# NBP5_Actel_ProASIC_Plus_PQ208_Rev1_01.net
KiCad netlist of a schematic drawn in Altium Designer
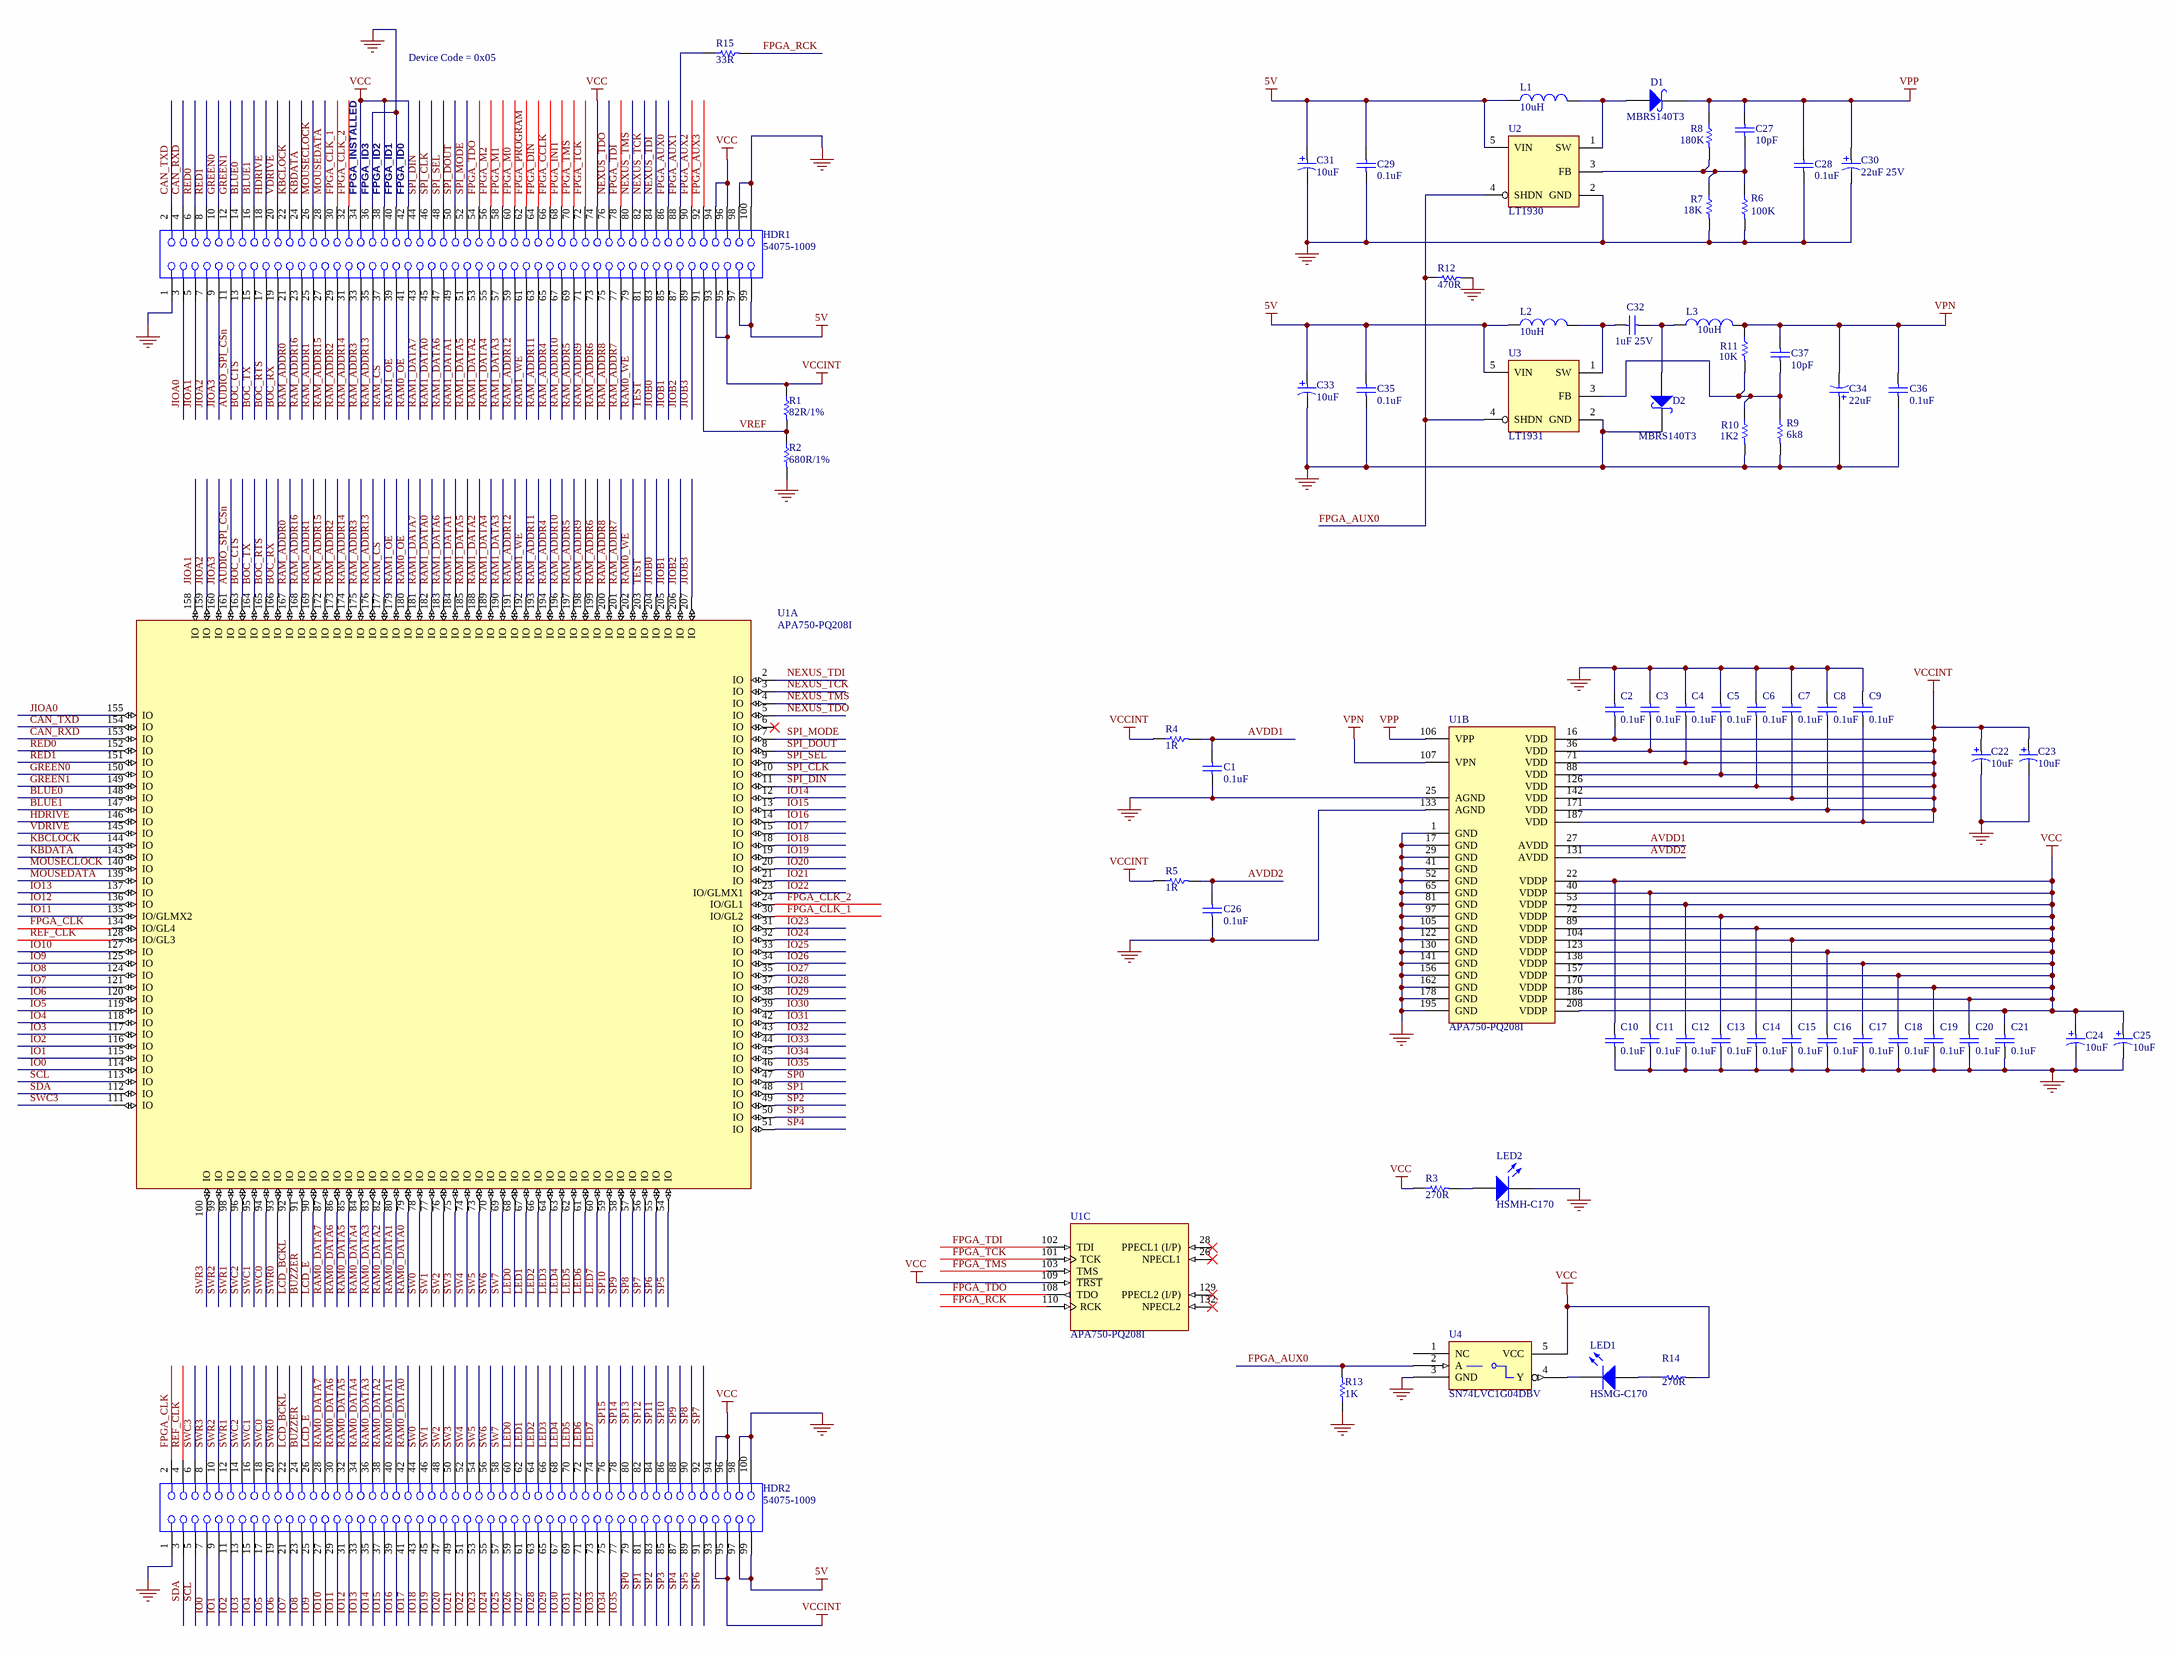
[diagram p0: NBP5 Actel ProASIC Plus PQ208 Rev1.01.SchDoc]

(export (version "E")
  (design (tool "Eeschema 10.0.6"))
  (components
    (comp (ref "C1")
      (value "0.1uF")
      (footprint "CC2012-0805")
      (description "Capacitor")
      (libsource (lib "PassiveSMD") (part "CAP"))
    )
    (comp (ref "C2")
      (value "0.1uF")
      (footprint "CC2012-0805")
      (description "Capacitor")
      (libsource (lib "PassiveSMD") (part "CAP"))
    )
    (comp (ref "C3")
      (value "0.1uF")
      (footprint "CC2012-0805")
      (description "Capacitor")
      (libsource (lib "PassiveSMD") (part "CAP"))
    )
    (comp (ref "C4")
      (value "0.1uF")
      (footprint "CC2012-0805")
      (description "Capacitor")
      (libsource (lib "PassiveSMD") (part "CAP"))
    )
    (comp (ref "C5")
      (value "0.1uF")
      (footprint "CC2012-0805")
      (description "Capacitor")
      (libsource (lib "PassiveSMD") (part "CAP"))
    )
    (comp (ref "C6")
      (value "0.1uF")
      (footprint "CC2012-0805")
      (description "Capacitor")
      (libsource (lib "PassiveSMD") (part "CAP"))
    )
    (comp (ref "C7")
      (value "0.1uF")
      (footprint "CC2012-0805")
      (description "Capacitor")
      (libsource (lib "PassiveSMD") (part "CAP"))
    )
    (comp (ref "C8")
      (value "0.1uF")
      (footprint "CC2012-0805")
      (description "Capacitor")
      (libsource (lib "PassiveSMD") (part "CAP"))
    )
    (comp (ref "C9")
      (value "0.1uF")
      (footprint "CC2012-0805")
      (description "Capacitor")
      (libsource (lib "PassiveSMD") (part "CAP"))
    )
    (comp (ref "C10")
      (value "0.1uF")
      (footprint "CC2012-0805")
      (description "Capacitor")
      (libsource (lib "PassiveSMD") (part "CAP"))
    )
    (comp (ref "C11")
      (value "0.1uF")
      (footprint "CC2012-0805")
      (description "Capacitor")
      (libsource (lib "PassiveSMD") (part "CAP"))
    )
    (comp (ref "C12")
      (value "0.1uF")
      (footprint "CC2012-0805")
      (description "Capacitor")
      (libsource (lib "PassiveSMD") (part "CAP"))
    )
    (comp (ref "C13")
      (value "0.1uF")
      (footprint "CC2012-0805")
      (description "Capacitor")
      (libsource (lib "PassiveSMD") (part "CAP"))
    )
    (comp (ref "C14")
      (value "0.1uF")
      (footprint "CC2012-0805")
      (description "Capacitor")
      (libsource (lib "PassiveSMD") (part "CAP"))
    )
    (comp (ref "C15")
      (value "0.1uF")
      (footprint "CC2012-0805")
      (description "Capacitor")
      (libsource (lib "PassiveSMD") (part "CAP"))
    )
    (comp (ref "C16")
      (value "0.1uF")
      (footprint "CC2012-0805")
      (description "Capacitor")
      (libsource (lib "PassiveSMD") (part "CAP"))
    )
    (comp (ref "C17")
      (value "0.1uF")
      (footprint "CC2012-0805")
      (description "Capacitor")
      (libsource (lib "PassiveSMD") (part "CAP"))
    )
    (comp (ref "C18")
      (value "0.1uF")
      (footprint "CC2012-0805")
      (description "Capacitor")
      (libsource (lib "PassiveSMD") (part "CAP"))
    )
    (comp (ref "C19")
      (value "0.1uF")
      (footprint "CC2012-0805")
      (description "Capacitor")
      (libsource (lib "PassiveSMD") (part "CAP"))
    )
    (comp (ref "C20")
      (value "0.1uF")
      (footprint "CC2012-0805")
      (description "Capacitor")
      (libsource (lib "PassiveSMD") (part "CAP"))
    )
    (comp (ref "C21")
      (value "0.1uF")
      (footprint "CC2012-0805")
      (description "Capacitor")
      (libsource (lib "PassiveSMD") (part "CAP"))
    )
    (comp (ref "C22")
      (value "10uF")
      (footprint "MCCT-B")
      (description "Polar Capacitor")
      (libsource (lib "PassiveSMD") (part "CAP_POLAR"))
    )
    (comp (ref "C23")
      (value "10uF")
      (footprint "MCCT-B")
      (description "Polar Capacitor")
      (libsource (lib "PassiveSMD") (part "CAP_POLAR"))
    )
    (comp (ref "C24")
      (value "10uF")
      (footprint "MCCT-B")
      (description "Polar Capacitor")
      (libsource (lib "PassiveSMD") (part "CAP_POLAR"))
    )
    (comp (ref "C25")
      (value "10uF")
      (footprint "MCCT-B")
      (description "Polar Capacitor")
      (libsource (lib "PassiveSMD") (part "CAP_POLAR"))
    )
    (comp (ref "C26")
      (value "0.1uF")
      (footprint "CC2012-0805")
      (description "Capacitor")
      (libsource (lib "PassiveSMD") (part "CAP"))
    )
    (comp (ref "C27")
      (value "10pF")
      (footprint "CC2012-0805")
      (description "Capacitor")
      (libsource (lib "PassiveSMD") (part "CAP"))
    )
    (comp (ref "C28")
      (value "0.1uF")
      (footprint "CC2012-0805")
      (description "Capacitor")
      (libsource (lib "PassiveSMD") (part "CAP"))
    )
    (comp (ref "C29")
      (value "0.1uF")
      (footprint "CC2012-0805")
      (description "Capacitor")
      (libsource (lib "PassiveSMD") (part "CAP"))
    )
    (comp (ref "C30")
      (value "22uF 25V")
      (footprint "MCCT-D")
      (description "Polar Capacitor")
      (libsource (lib "PassiveSMD") (part "CAP_POLAR"))
    )
    (comp (ref "C31")
      (value "10uF")
      (footprint "MCCT-B")
      (description "Polar Capacitor")
      (libsource (lib "PassiveSMD") (part "CAP_POLAR"))
    )
    (comp (ref "C32")
      (value "1uF 25V")
      (footprint "CC3216-1206")
      (description "Capacitor")
      (libsource (lib "PassiveSMD") (part "CAP"))
    )
    (comp (ref "C33")
      (value "10uF")
      (footprint "MCCT-B")
      (description "Polar Capacitor")
      (libsource (lib "PassiveSMD") (part "CAP_POLAR"))
    )
    (comp (ref "C34")
      (value "22uF")
      (footprint "MCCT-D")
      (description "Polar Capacitor")
      (libsource (lib "PassiveSMD") (part "CAP_POLAR"))
    )
    (comp (ref "C35")
      (value "0.1uF")
      (footprint "CC2012-0805")
      (description "Capacitor")
      (libsource (lib "PassiveSMD") (part "CAP"))
    )
    (comp (ref "C36")
      (value "0.1uF")
      (footprint "CC2012-0805")
      (description "Capacitor")
      (libsource (lib "PassiveSMD") (part "CAP"))
    )
    (comp (ref "C37")
      (value "10pF")
      (footprint "CC2012-0805")
      (description "Capacitor")
      (libsource (lib "PassiveSMD") (part "CAP"))
    )
    (comp (ref "D1")
      (value "MBRS140T3")
      (footprint "403A")
      (description "Shottky Diode")
      (libsource (lib "Diodes") (part "Shottky"))
    )
    (comp (ref "D2")
      (value "MBRS140T3")
      (footprint "403A")
      (description "Shottky Diode")
      (libsource (lib "Diodes") (part "Shottky"))
    )
    (comp (ref "HDR1")
      (value "54075-1009")
      (footprint "54075")
      (fields
        (field (name "MANUFACTURER") "Molex")
        (field (name "VOLTAGE") "100V")
        (field (name "PUBLISHER") "Altium Limited")
      )
      (libsource (lib "Altium Nanoboard Project") (part "54075-1009"))
    )
    (comp (ref "HDR2")
      (value "54075-1009")
      (footprint "54075")
      (fields
        (field (name "MANUFACTURER") "Molex")
        (field (name "VOLTAGE") "100V")
        (field (name "PUBLISHER") "Altium Limited")
      )
      (libsource (lib "Altium Nanoboard Project") (part "54075-1009"))
    )
    (comp (ref "L1")
      (value "10uH")
      (footprint "CC4532-1812")
      (description "Inductor")
      (libsource (lib "PassiveSMD") (part "INDUCTOR"))
    )
    (comp (ref "L2")
      (value "10uH")
      (footprint "CC4532-1812")
      (description "Inductor")
      (libsource (lib "PassiveSMD") (part "INDUCTOR"))
    )
    (comp (ref "L3")
      (value "10uH")
      (footprint "CC4532-1812")
      (description "Inductor")
      (libsource (lib "PassiveSMD") (part "INDUCTOR"))
    )
    (comp (ref "LED1")
      (value "HSMG-C170")
      (footprint "SMD _LED")
      (description "Typical RED GaAs SMD LED Agilent make")
      (fields (field (name "MANUFACTURER") "Generic Components") (field (name "PUBLISHER") "Altium Limited"))
      (libsource (lib "Switches and display") (part "HSMX-C670"))
    )
    (comp (ref "LED2")
      (value "HSMH-C170")
      (footprint "SMD _LED")
      (description "Typical RED GaAs SMD LED Agilent make")
      (fields (field (name "MANUFACTURER") "Generic Components") (field (name "PUBLISHER") "Altium Limited"))
      (libsource (lib "Switches and display") (part "HSMX-C670"))
    )
    (comp (ref "R1")
      (value "82R/1%")
      (footprint "CC2012-0805")
      (description "Resistor")
      (libsource (lib "PassiveSMD") (part "RES"))
    )
    (comp (ref "R2")
      (value "680R/1%")
      (footprint "CC2012-0805")
      (description "Resistor")
      (libsource (lib "PassiveSMD") (part "RES"))
    )
    (comp (ref "R3")
      (value "270R")
      (footprint "CC2012-0805")
      (description "Resistor")
      (libsource (lib "PassiveSMD") (part "RES"))
    )
    (comp (ref "R4")
      (value "1R")
      (footprint "CC2012-0805")
      (description "Resistor")
      (libsource (lib "PassiveSMD") (part "RES"))
    )
    (comp (ref "R5")
      (value "1R")
      (footprint "CC2012-0805")
      (description "Resistor")
      (libsource (lib "PassiveSMD") (part "RES"))
    )
    (comp (ref "R6")
      (value "100K")
      (footprint "CC2012-0805")
      (description "Resistor")
      (libsource (lib "PassiveSMD") (part "RES"))
    )
    (comp (ref "R7")
      (value "18K")
      (footprint "CC2012-0805")
      (description "Resistor")
      (libsource (lib "PassiveSMD") (part "RES"))
    )
    (comp (ref "R8")
      (value "180K")
      (footprint "CC2012-0805")
      (description "Resistor")
      (libsource (lib "PassiveSMD") (part "RES"))
    )
    (comp (ref "R9")
      (value "6k8")
      (footprint "CC2012-0805")
      (description "Resistor")
      (libsource (lib "PassiveSMD") (part "RES"))
    )
    (comp (ref "R10")
      (value "1K2")
      (footprint "CC2012-0805")
      (description "Resistor")
      (libsource (lib "PassiveSMD") (part "RES"))
    )
    (comp (ref "R11")
      (value "10K")
      (footprint "CC2012-0805")
      (description "Resistor")
      (libsource (lib "PassiveSMD") (part "RES"))
    )
    (comp (ref "R12")
      (value "470R")
      (footprint "CC2012-0805")
      (description "Resistor")
      (libsource (lib "PassiveSMD") (part "RES"))
    )
    (comp (ref "R13")
      (value "1K")
      (footprint "CC2012-0805")
      (description "Resistor")
      (libsource (lib "PassiveSMD") (part "RES"))
    )
    (comp (ref "R14")
      (value "270R")
      (footprint "CC2012-0805")
      (description "Resistor")
      (libsource (lib "PassiveSMD") (part "RES"))
    )
    (comp (ref "R15")
      (value "33R")
      (footprint "CC2012-0805")
      (description "Resistor")
      (libsource (lib "PassiveSMD") (part "RES"))
    )
    (comp (ref "U1")
      (value "APA750-PQ208I")
      (footprint "PQ208")
      (description "ProASICPlus APA750 Flash FPGA, 156 User IOs, 208-Pin PQFP, Speed Grade Standard, Industrial Grade")
      (fields (field (name "PUBLISHER") "Altium Limited"))
      (libsource (lib "ActelAPA_FPGA") (part "APA750-PQ208I"))
    )
    (comp (ref "U2")
      (value "LT1930")
      (footprint "SO-G5/P.95")
      (description "Switching Regulator")
      (fields (field (name "MANUFACTURER") "Linear Technology"))
      (libsource (lib "LT_Switching_Regulators") (part "LT1930"))
    )
    (comp (ref "U3")
      (value "LT1931")
      (footprint "SO-G5/P.95")
      (description "Switching Regulator")
      (fields (field (name "MANUFACTURER") "Linear Technology"))
      (libsource (lib "LT_Switching_Regulators") (part "LT1931"))
    )
    (comp (ref "U4")
      (value "SN74LVC1G04DBV")
      (footprint "SO-G5/P.95")
      (fields (field (name "MANUFACTURER") "TI"))
      (libsource (lib "Philips1GLogic") (part "SN74AHC1G04DBVR"))
    )
  )
  (nets
    (net (code "1") (name "/AUDIO_SPI_CSn") (class "Default")
      (node (ref "HDR1") (pin "11") (pinfunction "11_11") (pintype "passive"))
      (node (ref "U1") (pin "161") (pinfunction "IO_161") (pintype "bidirectional"))
    )
    (net (code "2") (name "/AVDD1") (class "Default")
      (node (ref "C1") (pin "1") (pinfunction "1_1") (pintype "passive"))
      (node (ref "R4") (pin "2") (pinfunction "2_2") (pintype "passive"))
      (node (ref "U1") (pin "27") (pinfunction "AVDD_27") (pintype "power_in"))
    )
    (net (code "3") (name "/AVDD2") (class "Default")
      (node (ref "C26") (pin "1") (pinfunction "1_1") (pintype "passive"))
      (node (ref "R5") (pin "2") (pinfunction "2_2") (pintype "passive"))
      (node (ref "U1") (pin "131") (pinfunction "AVDD_131") (pintype "power_in"))
    )
    (net (code "4") (name "/BLUE0") (class "Default")
      (node (ref "HDR1") (pin "14") (pinfunction "14_14") (pintype "passive"))
      (node (ref "U1") (pin "148") (pinfunction "IO_148") (pintype "bidirectional"))
    )
    (net (code "5") (name "/BLUE1") (class "Default")
      (node (ref "HDR1") (pin "16") (pinfunction "16_16") (pintype "passive"))
      (node (ref "U1") (pin "147") (pinfunction "IO_147") (pintype "bidirectional"))
    )
    (net (code "6") (name "/BOC_CTS") (class "Default")
      (node (ref "HDR1") (pin "13") (pinfunction "13_13") (pintype "passive"))
      (node (ref "U1") (pin "163") (pinfunction "IO_163") (pintype "bidirectional"))
    )
    (net (code "7") (name "/BOC_RTS") (class "Default")
      (node (ref "HDR1") (pin "17") (pinfunction "17_17") (pintype "passive"))
      (node (ref "U1") (pin "165") (pinfunction "IO_165") (pintype "bidirectional"))
    )
    (net (code "8") (name "/BOC_RX") (class "Default")
      (node (ref "HDR1") (pin "19") (pinfunction "19_19") (pintype "passive"))
      (node (ref "U1") (pin "166") (pinfunction "IO_166") (pintype "bidirectional"))
    )
    (net (code "9") (name "/BOC_TX") (class "Default")
      (node (ref "HDR1") (pin "15") (pinfunction "15_15") (pintype "passive"))
      (node (ref "U1") (pin "164") (pinfunction "IO_164") (pintype "bidirectional"))
    )
    (net (code "10") (name "/BUZZER") (class "Default")
      (node (ref "HDR2") (pin "24") (pinfunction "24_24") (pintype "passive"))
      (node (ref "U1") (pin "91") (pinfunction "IO_91") (pintype "bidirectional"))
    )
    (net (code "11") (name "/CAN_RXD") (class "Default")
      (node (ref "HDR1") (pin "4") (pinfunction "4_4") (pintype "passive"))
      (node (ref "U1") (pin "153") (pinfunction "IO_153") (pintype "bidirectional"))
    )
    (net (code "12") (name "/CAN_TXD") (class "Default")
      (node (ref "HDR1") (pin "2") (pinfunction "2_2") (pintype "passive"))
      (node (ref "U1") (pin "154") (pinfunction "IO_154") (pintype "bidirectional"))
    )
    (net (code "13") (name "/FPGA_AUX0") (class "Default")
      (node (ref "HDR1") (pin "86") (pinfunction "86_86") (pintype "passive"))
      (node (ref "R12") (pin "1") (pinfunction "1_1") (pintype "passive"))
      (node (ref "R13") (pin "2") (pinfunction "2_2") (pintype "passive"))
      (node (ref "U2") (pin "4") (pinfunction "SHDN_4") (pintype "passive"))
      (node (ref "U3") (pin "4") (pinfunction "SHDN_4") (pintype "passive"))
      (node (ref "U4") (pin "2") (pinfunction "A_2") (pintype "input"))
    )
    (net (code "14") (name "/FPGA_AUX1") (class "Default")
      (node (ref "HDR1") (pin "88") (pinfunction "88_88") (pintype "passive"))
      (node (ref "R15") (pin "1") (pinfunction "1_1") (pintype "passive"))
    )
    (net (code "15") (name "/FPGA_AUX2") (class "Default")
      (node (ref "HDR1") (pin "90") (pinfunction "90_90") (pintype "passive"))
    )
    (net (code "16") (name "/FPGA_AUX3") (class "Default")
      (node (ref "HDR1") (pin "92") (pinfunction "92_92") (pintype "passive"))
    )
    (net (code "17") (name "/FPGA_CCLK") (class "Default")
      (node (ref "HDR1") (pin "66") (pinfunction "66_66") (pintype "passive"))
    )
    (net (code "18") (name "/FPGA_CLK") (class "Default")
      (node (ref "HDR2") (pin "2") (pinfunction "2_2") (pintype "passive"))
      (node (ref "U1") (pin "134") (pinfunction "IO/GL4_134") (pintype "bidirectional"))
    )
    (net (code "19") (name "/FPGA_CLK_1") (class "Default")
      (node (ref "HDR1") (pin "30") (pinfunction "30_30") (pintype "passive"))
      (node (ref "U1") (pin "30") (pinfunction "IO/GL2_30") (pintype "bidirectional"))
    )
    (net (code "20") (name "/FPGA_CLK_2") (class "Default")
      (node (ref "HDR1") (pin "32") (pinfunction "32_32") (pintype "passive"))
      (node (ref "U1") (pin "24") (pinfunction "IO/GL1_24") (pintype "bidirectional"))
    )
    (net (code "21") (name "/FPGA_DIN") (class "Default")
      (node (ref "HDR1") (pin "64") (pinfunction "64_64") (pintype "passive"))
    )
    (net (code "22") (name "/FPGA_INIT") (class "Default")
      (node (ref "HDR1") (pin "68") (pinfunction "68_68") (pintype "passive"))
    )
    (net (code "23") (name "/FPGA_M0") (class "Default")
      (node (ref "HDR1") (pin "60") (pinfunction "60_60") (pintype "passive"))
    )
    (net (code "24") (name "/FPGA_M1") (class "Default")
      (node (ref "HDR1") (pin "58") (pinfunction "58_58") (pintype "passive"))
    )
    (net (code "25") (name "/FPGA_M2") (class "Default")
      (node (ref "HDR1") (pin "56") (pinfunction "56_56") (pintype "passive"))
    )
    (net (code "26") (name "/FPGA_PROGRAM") (class "Default")
      (node (ref "HDR1") (pin "62") (pinfunction "62_62") (pintype "passive"))
    )
    (net (code "27") (name "/FPGA_RCK") (class "Default")
      (node (ref "R15") (pin "2") (pinfunction "2_2") (pintype "passive"))
      (node (ref "U1") (pin "110") (pinfunction "RCK_110") (pintype "input"))
    )
    (net (code "28") (name "/FPGA_TCK") (class "Default")
      (node (ref "HDR1") (pin "72") (pinfunction "72_72") (pintype "passive"))
      (node (ref "U1") (pin "101") (pinfunction "TCK_101") (pintype "input"))
    )
    (net (code "29") (name "/FPGA_TDI") (class "Default")
      (node (ref "HDR1") (pin "78") (pinfunction "78_78") (pintype "passive"))
      (node (ref "U1") (pin "102") (pinfunction "TDI_102") (pintype "input"))
    )
    (net (code "30") (name "/FPGA_TDO") (class "Default")
      (node (ref "HDR1") (pin "54") (pinfunction "54_54") (pintype "passive"))
      (node (ref "U1") (pin "108") (pinfunction "TDO_108") (pintype "output"))
    )
    (net (code "31") (name "/FPGA_TMS") (class "Default")
      (node (ref "HDR1") (pin "70") (pinfunction "70_70") (pintype "passive"))
      (node (ref "U1") (pin "103") (pinfunction "TMS_103") (pintype "input"))
    )
    (net (code "32") (name "/GREEN0") (class "Default")
      (node (ref "HDR1") (pin "10") (pinfunction "10_10") (pintype "passive"))
      (node (ref "U1") (pin "150") (pinfunction "IO_150") (pintype "bidirectional"))
    )
    (net (code "33") (name "/GREEN1") (class "Default")
      (node (ref "HDR1") (pin "12") (pinfunction "12_12") (pintype "passive"))
      (node (ref "U1") (pin "149") (pinfunction "IO_149") (pintype "bidirectional"))
    )
    (net (code "34") (name "/HDRIVE") (class "Default")
      (node (ref "HDR1") (pin "18") (pinfunction "18_18") (pintype "passive"))
      (node (ref "U1") (pin "146") (pinfunction "IO_146") (pintype "bidirectional"))
    )
    (net (code "35") (name "/IO0") (class "Default")
      (node (ref "HDR2") (pin "7") (pinfunction "7_7") (pintype "passive"))
      (node (ref "U1") (pin "114") (pinfunction "IO_114") (pintype "bidirectional"))
    )
    (net (code "36") (name "/IO1") (class "Default")
      (node (ref "HDR2") (pin "9") (pinfunction "9_9") (pintype "passive"))
      (node (ref "U1") (pin "115") (pinfunction "IO_115") (pintype "bidirectional"))
    )
    (net (code "37") (name "/IO2") (class "Default")
      (node (ref "HDR2") (pin "11") (pinfunction "11_11") (pintype "passive"))
      (node (ref "U1") (pin "116") (pinfunction "IO_116") (pintype "bidirectional"))
    )
    (net (code "38") (name "/IO3") (class "Default")
      (node (ref "HDR2") (pin "13") (pinfunction "13_13") (pintype "passive"))
      (node (ref "U1") (pin "117") (pinfunction "IO_117") (pintype "bidirectional"))
    )
    (net (code "39") (name "/IO4") (class "Default")
      (node (ref "HDR2") (pin "15") (pinfunction "15_15") (pintype "passive"))
      (node (ref "U1") (pin "118") (pinfunction "IO_118") (pintype "bidirectional"))
    )
    (net (code "40") (name "/IO5") (class "Default")
      (node (ref "HDR2") (pin "17") (pinfunction "17_17") (pintype "passive"))
      (node (ref "U1") (pin "119") (pinfunction "IO_119") (pintype "bidirectional"))
    )
    (net (code "41") (name "/IO6") (class "Default")
      (node (ref "HDR2") (pin "19") (pinfunction "19_19") (pintype "passive"))
      (node (ref "U1") (pin "120") (pinfunction "IO_120") (pintype "bidirectional"))
    )
    (net (code "42") (name "/IO7") (class "Default")
      (node (ref "HDR2") (pin "21") (pinfunction "21_21") (pintype "passive"))
      (node (ref "U1") (pin "121") (pinfunction "IO_121") (pintype "bidirectional"))
    )
    (net (code "43") (name "/IO8") (class "Default")
      (node (ref "HDR2") (pin "23") (pinfunction "23_23") (pintype "passive"))
      (node (ref "U1") (pin "124") (pinfunction "IO_124") (pintype "bidirectional"))
    )
    (net (code "44") (name "/IO9") (class "Default")
      (node (ref "HDR2") (pin "25") (pinfunction "25_25") (pintype "passive"))
      (node (ref "U1") (pin "125") (pinfunction "IO_125") (pintype "bidirectional"))
    )
    (net (code "45") (name "/IO10") (class "Default")
      (node (ref "HDR2") (pin "27") (pinfunction "27_27") (pintype "passive"))
      (node (ref "U1") (pin "127") (pinfunction "IO_127") (pintype "bidirectional"))
    )
    (net (code "46") (name "/IO11") (class "Default")
      (node (ref "HDR2") (pin "29") (pinfunction "29_29") (pintype "passive"))
      (node (ref "U1") (pin "135") (pinfunction "IO/GLMX2_135") (pintype "bidirectional"))
    )
    (net (code "47") (name "/IO12") (class "Default")
      (node (ref "HDR2") (pin "31") (pinfunction "31_31") (pintype "passive"))
      (node (ref "U1") (pin "136") (pinfunction "IO_136") (pintype "bidirectional"))
    )
    (net (code "48") (name "/IO13") (class "Default")
      (node (ref "HDR2") (pin "33") (pinfunction "33_33") (pintype "passive"))
      (node (ref "U1") (pin "137") (pinfunction "IO_137") (pintype "bidirectional"))
    )
    (net (code "49") (name "/IO14") (class "Default")
      (node (ref "HDR2") (pin "35") (pinfunction "35_35") (pintype "passive"))
      (node (ref "U1") (pin "12") (pinfunction "IO_12") (pintype "bidirectional"))
    )
    (net (code "50") (name "/IO15") (class "Default")
      (node (ref "HDR2") (pin "37") (pinfunction "37_37") (pintype "passive"))
      (node (ref "U1") (pin "13") (pinfunction "IO_13") (pintype "bidirectional"))
    )
    (net (code "51") (name "/IO16") (class "Default")
      (node (ref "HDR2") (pin "39") (pinfunction "39_39") (pintype "passive"))
      (node (ref "U1") (pin "14") (pinfunction "IO_14") (pintype "bidirectional"))
    )
    (net (code "52") (name "/IO17") (class "Default")
      (node (ref "HDR2") (pin "41") (pinfunction "41_41") (pintype "passive"))
      (node (ref "U1") (pin "15") (pinfunction "IO_15") (pintype "bidirectional"))
    )
    (net (code "53") (name "/IO18") (class "Default")
      (node (ref "HDR2") (pin "43") (pinfunction "43_43") (pintype "passive"))
      (node (ref "U1") (pin "18") (pinfunction "IO_18") (pintype "bidirectional"))
    )
    (net (code "54") (name "/IO19") (class "Default")
      (node (ref "HDR2") (pin "45") (pinfunction "45_45") (pintype "passive"))
      (node (ref "U1") (pin "19") (pinfunction "IO_19") (pintype "bidirectional"))
    )
    (net (code "55") (name "/IO20") (class "Default")
      (node (ref "HDR2") (pin "47") (pinfunction "47_47") (pintype "passive"))
      (node (ref "U1") (pin "20") (pinfunction "IO_20") (pintype "bidirectional"))
    )
    (net (code "56") (name "/IO21") (class "Default")
      (node (ref "HDR2") (pin "49") (pinfunction "49_49") (pintype "passive"))
      (node (ref "U1") (pin "21") (pinfunction "IO_21") (pintype "bidirectional"))
    )
    (net (code "57") (name "/IO22") (class "Default")
      (node (ref "HDR2") (pin "51") (pinfunction "51_51") (pintype "passive"))
      (node (ref "U1") (pin "23") (pinfunction "IO/GLMX1_23") (pintype "bidirectional"))
    )
    (net (code "58") (name "/IO23") (class "Default")
      (node (ref "HDR2") (pin "53") (pinfunction "53_53") (pintype "passive"))
      (node (ref "U1") (pin "31") (pinfunction "IO_31") (pintype "bidirectional"))
    )
    (net (code "59") (name "/IO24") (class "Default")
      (node (ref "HDR2") (pin "55") (pinfunction "55_55") (pintype "passive"))
      (node (ref "U1") (pin "32") (pinfunction "IO_32") (pintype "bidirectional"))
    )
    (net (code "60") (name "/IO25") (class "Default")
      (node (ref "HDR2") (pin "57") (pinfunction "57_57") (pintype "passive"))
      (node (ref "U1") (pin "33") (pinfunction "IO_33") (pintype "bidirectional"))
    )
    (net (code "61") (name "/IO26") (class "Default")
      (node (ref "HDR2") (pin "59") (pinfunction "59_59") (pintype "passive"))
      (node (ref "U1") (pin "34") (pinfunction "IO_34") (pintype "bidirectional"))
    )
    (net (code "62") (name "/IO27") (class "Default")
      (node (ref "HDR2") (pin "61") (pinfunction "61_61") (pintype "passive"))
      (node (ref "U1") (pin "35") (pinfunction "IO_35") (pintype "bidirectional"))
    )
    (net (code "63") (name "/IO28") (class "Default")
      (node (ref "HDR2") (pin "63") (pinfunction "63_63") (pintype "passive"))
      (node (ref "U1") (pin "37") (pinfunction "IO_37") (pintype "bidirectional"))
    )
    (net (code "64") (name "/IO29") (class "Default")
      (node (ref "HDR2") (pin "65") (pinfunction "65_65") (pintype "passive"))
      (node (ref "U1") (pin "38") (pinfunction "IO_38") (pintype "bidirectional"))
    )
    (net (code "65") (name "/IO30") (class "Default")
      (node (ref "HDR2") (pin "67") (pinfunction "67_67") (pintype "passive"))
      (node (ref "U1") (pin "39") (pinfunction "IO_39") (pintype "bidirectional"))
    )
    (net (code "66") (name "/IO31") (class "Default")
      (node (ref "HDR2") (pin "69") (pinfunction "69_69") (pintype "passive"))
      (node (ref "U1") (pin "42") (pinfunction "IO_42") (pintype "bidirectional"))
    )
    (net (code "67") (name "/IO32") (class "Default")
      (node (ref "HDR2") (pin "71") (pinfunction "71_71") (pintype "passive"))
      (node (ref "U1") (pin "43") (pinfunction "IO_43") (pintype "bidirectional"))
    )
    (net (code "68") (name "/IO33") (class "Default")
      (node (ref "HDR2") (pin "73") (pinfunction "73_73") (pintype "passive"))
      (node (ref "U1") (pin "44") (pinfunction "IO_44") (pintype "bidirectional"))
    )
    (net (code "69") (name "/IO34") (class "Default")
      (node (ref "HDR2") (pin "75") (pinfunction "75_75") (pintype "passive"))
      (node (ref "U1") (pin "45") (pinfunction "IO_45") (pintype "bidirectional"))
    )
    (net (code "70") (name "/IO35") (class "Default")
      (node (ref "HDR2") (pin "77") (pinfunction "77_77") (pintype "passive"))
      (node (ref "U1") (pin "46") (pinfunction "IO_46") (pintype "bidirectional"))
    )
    (net (code "71") (name "/JIOA0") (class "Default")
      (node (ref "HDR1") (pin "3") (pinfunction "3_3") (pintype "passive"))
      (node (ref "U1") (pin "155") (pinfunction "IO_155") (pintype "bidirectional"))
    )
    (net (code "72") (name "/JIOA1") (class "Default")
      (node (ref "HDR1") (pin "5") (pinfunction "5_5") (pintype "passive"))
      (node (ref "U1") (pin "158") (pinfunction "IO_158") (pintype "bidirectional"))
    )
    (net (code "73") (name "/JIOA2") (class "Default")
      (node (ref "HDR1") (pin "7") (pinfunction "7_7") (pintype "passive"))
      (node (ref "U1") (pin "159") (pinfunction "IO_159") (pintype "bidirectional"))
    )
    (net (code "74") (name "/JIOA3") (class "Default")
      (node (ref "HDR1") (pin "9") (pinfunction "9_9") (pintype "passive"))
      (node (ref "U1") (pin "160") (pinfunction "IO_160") (pintype "bidirectional"))
    )
    (net (code "75") (name "/JIOB0") (class "Default")
      (node (ref "HDR1") (pin "83") (pinfunction "83_83") (pintype "passive"))
      (node (ref "U1") (pin "204") (pinfunction "IO_204") (pintype "bidirectional"))
    )
    (net (code "76") (name "/JIOB1") (class "Default")
      (node (ref "HDR1") (pin "85") (pinfunction "85_85") (pintype "passive"))
      (node (ref "U1") (pin "205") (pinfunction "IO_205") (pintype "bidirectional"))
    )
    (net (code "77") (name "/JIOB2") (class "Default")
      (node (ref "HDR1") (pin "87") (pinfunction "87_87") (pintype "passive"))
      (node (ref "U1") (pin "206") (pinfunction "IO_206") (pintype "bidirectional"))
    )
    (net (code "78") (name "/JIOB3") (class "Default")
      (node (ref "HDR1") (pin "89") (pinfunction "89_89") (pintype "passive"))
      (node (ref "U1") (pin "207") (pinfunction "IO_207") (pintype "bidirectional"))
    )
    (net (code "79") (name "/KBCLOCK") (class "Default")
      (node (ref "HDR1") (pin "22") (pinfunction "22_22") (pintype "passive"))
      (node (ref "U1") (pin "144") (pinfunction "IO_144") (pintype "bidirectional"))
    )
    (net (code "80") (name "/KBDATA") (class "Default")
      (node (ref "HDR1") (pin "24") (pinfunction "24_24") (pintype "passive"))
      (node (ref "U1") (pin "143") (pinfunction "IO_143") (pintype "bidirectional"))
    )
    (net (code "81") (name "/LCD_BCKL") (class "Default")
      (node (ref "HDR2") (pin "22") (pinfunction "22_22") (pintype "passive"))
      (node (ref "U1") (pin "92") (pinfunction "IO_92") (pintype "bidirectional"))
    )
    (net (code "82") (name "/LCD_E") (class "Default")
      (node (ref "HDR2") (pin "26") (pinfunction "26_26") (pintype "passive"))
      (node (ref "U1") (pin "90") (pinfunction "IO_90") (pintype "bidirectional"))
    )
    (net (code "83") (name "/LED0") (class "Default")
      (node (ref "HDR2") (pin "60") (pinfunction "60_60") (pintype "passive"))
      (node (ref "U1") (pin "68") (pinfunction "IO_68") (pintype "bidirectional"))
    )
    (net (code "84") (name "/LED1") (class "Default")
      (node (ref "HDR2") (pin "62") (pinfunction "62_62") (pintype "passive"))
      (node (ref "U1") (pin "67") (pinfunction "IO_67") (pintype "bidirectional"))
    )
    (net (code "85") (name "/LED2") (class "Default")
      (node (ref "HDR2") (pin "64") (pinfunction "64_64") (pintype "passive"))
      (node (ref "U1") (pin "66") (pinfunction "IO_66") (pintype "bidirectional"))
    )
    (net (code "86") (name "/LED3") (class "Default")
      (node (ref "HDR2") (pin "66") (pinfunction "66_66") (pintype "passive"))
      (node (ref "U1") (pin "64") (pinfunction "IO_64") (pintype "bidirectional"))
    )
    (net (code "87") (name "/LED4") (class "Default")
      (node (ref "HDR2") (pin "68") (pinfunction "68_68") (pintype "passive"))
      (node (ref "U1") (pin "63") (pinfunction "IO_63") (pintype "bidirectional"))
    )
    (net (code "88") (name "/LED5") (class "Default")
      (node (ref "HDR2") (pin "70") (pinfunction "70_70") (pintype "passive"))
      (node (ref "U1") (pin "62") (pinfunction "IO_62") (pintype "bidirectional"))
    )
    (net (code "89") (name "/LED6") (class "Default")
      (node (ref "HDR2") (pin "72") (pinfunction "72_72") (pintype "passive"))
      (node (ref "U1") (pin "61") (pinfunction "IO_61") (pintype "bidirectional"))
    )
    (net (code "90") (name "/LED7") (class "Default")
      (node (ref "HDR2") (pin "74") (pinfunction "74_74") (pintype "passive"))
      (node (ref "U1") (pin "60") (pinfunction "IO_60") (pintype "bidirectional"))
    )
    (net (code "91") (name "/MOUSECLOCK") (class "Default")
      (node (ref "HDR1") (pin "26") (pinfunction "26_26") (pintype "passive"))
      (node (ref "U1") (pin "140") (pinfunction "IO_140") (pintype "bidirectional"))
    )
    (net (code "92") (name "/MOUSEDATA") (class "Default")
      (node (ref "HDR1") (pin "28") (pinfunction "28_28") (pintype "passive"))
      (node (ref "U1") (pin "139") (pinfunction "IO_139") (pintype "bidirectional"))
    )
    (net (code "93") (name "/NEXUS_TCK") (class "Default")
      (node (ref "HDR1") (pin "82") (pinfunction "82_82") (pintype "passive"))
      (node (ref "U1") (pin "3") (pinfunction "IO_3") (pintype "bidirectional"))
    )
    (net (code "94") (name "/NEXUS_TDI") (class "Default")
      (node (ref "HDR1") (pin "84") (pinfunction "84_84") (pintype "passive"))
      (node (ref "U1") (pin "2") (pinfunction "IO_2") (pintype "bidirectional"))
    )
    (net (code "95") (name "/NEXUS_TDO") (class "Default")
      (node (ref "HDR1") (pin "76") (pinfunction "76_76") (pintype "passive"))
      (node (ref "U1") (pin "5") (pinfunction "IO_5") (pintype "bidirectional"))
    )
    (net (code "96") (name "/NEXUS_TMS") (class "Default")
      (node (ref "HDR1") (pin "80") (pinfunction "80_80") (pintype "passive"))
      (node (ref "U1") (pin "4") (pinfunction "IO_4") (pintype "bidirectional"))
    )
    (net (code "97") (name "/RAM0_DATA0") (class "Default")
      (node (ref "HDR2") (pin "42") (pinfunction "42_42") (pintype "passive"))
      (node (ref "U1") (pin "79") (pinfunction "IO_79") (pintype "bidirectional"))
    )
    (net (code "98") (name "/RAM0_DATA1") (class "Default")
      (node (ref "HDR2") (pin "40") (pinfunction "40_40") (pintype "passive"))
      (node (ref "U1") (pin "80") (pinfunction "IO_80") (pintype "bidirectional"))
    )
    (net (code "99") (name "/RAM0_DATA2") (class "Default")
      (node (ref "HDR2") (pin "38") (pinfunction "38_38") (pintype "passive"))
      (node (ref "U1") (pin "82") (pinfunction "IO_82") (pintype "bidirectional"))
    )
    (net (code "100") (name "/RAM0_DATA3") (class "Default")
      (node (ref "HDR2") (pin "36") (pinfunction "36_36") (pintype "passive"))
      (node (ref "U1") (pin "83") (pinfunction "IO_83") (pintype "bidirectional"))
    )
    (net (code "101") (name "/RAM0_DATA4") (class "Default")
      (node (ref "HDR2") (pin "34") (pinfunction "34_34") (pintype "passive"))
      (node (ref "U1") (pin "84") (pinfunction "IO_84") (pintype "bidirectional"))
    )
    (net (code "102") (name "/RAM0_DATA5") (class "Default")
      (node (ref "HDR2") (pin "32") (pinfunction "32_32") (pintype "passive"))
      (node (ref "U1") (pin "85") (pinfunction "IO_85") (pintype "bidirectional"))
    )
    (net (code "103") (name "/RAM0_DATA6") (class "Default")
      (node (ref "HDR2") (pin "30") (pinfunction "30_30") (pintype "passive"))
      (node (ref "U1") (pin "86") (pinfunction "IO_86") (pintype "bidirectional"))
    )
    (net (code "104") (name "/RAM0_DATA7") (class "Default")
      (node (ref "HDR2") (pin "28") (pinfunction "28_28") (pintype "passive"))
      (node (ref "U1") (pin "87") (pinfunction "IO_87") (pintype "bidirectional"))
    )
    (net (code "105") (name "/RAM0_OE") (class "Default")
      (node (ref "HDR1") (pin "41") (pinfunction "41_41") (pintype "passive"))
      (node (ref "U1") (pin "180") (pinfunction "IO_180") (pintype "bidirectional"))
    )
    (net (code "106") (name "/RAM0_WE") (class "Default")
      (node (ref "HDR1") (pin "79") (pinfunction "79_79") (pintype "passive"))
      (node (ref "U1") (pin "202") (pinfunction "IO_202") (pintype "bidirectional"))
    )
    (net (code "107") (name "/RAM1_DATA0") (class "Default")
      (node (ref "HDR1") (pin "45") (pinfunction "45_45") (pintype "passive"))
      (node (ref "U1") (pin "182") (pinfunction "IO_182") (pintype "bidirectional"))
    )
    (net (code "108") (name "/RAM1_DATA1") (class "Default")
      (node (ref "HDR1") (pin "49") (pinfunction "49_49") (pintype "passive"))
      (node (ref "U1") (pin "184") (pinfunction "IO_184") (pintype "bidirectional"))
    )
    (net (code "109") (name "/RAM1_DATA2") (class "Default")
      (node (ref "HDR1") (pin "53") (pinfunction "53_53") (pintype "passive"))
      (node (ref "U1") (pin "188") (pinfunction "IO_188") (pintype "bidirectional"))
    )
    (net (code "110") (name "/RAM1_DATA3") (class "Default")
      (node (ref "HDR1") (pin "57") (pinfunction "57_57") (pintype "passive"))
      (node (ref "U1") (pin "190") (pinfunction "IO_190") (pintype "bidirectional"))
    )
    (net (code "111") (name "/RAM1_DATA4") (class "Default")
      (node (ref "HDR1") (pin "55") (pinfunction "55_55") (pintype "passive"))
      (node (ref "U1") (pin "189") (pinfunction "IO_189") (pintype "bidirectional"))
    )
    (net (code "112") (name "/RAM1_DATA5") (class "Default")
      (node (ref "HDR1") (pin "51") (pinfunction "51_51") (pintype "passive"))
      (node (ref "U1") (pin "185") (pinfunction "IO_185") (pintype "bidirectional"))
    )
    (net (code "113") (name "/RAM1_DATA6") (class "Default")
      (node (ref "HDR1") (pin "47") (pinfunction "47_47") (pintype "passive"))
      (node (ref "U1") (pin "183") (pinfunction "IO_183") (pintype "bidirectional"))
    )
    (net (code "114") (name "/RAM1_DATA7") (class "Default")
      (node (ref "HDR1") (pin "43") (pinfunction "43_43") (pintype "passive"))
      (node (ref "U1") (pin "181") (pinfunction "IO_181") (pintype "bidirectional"))
    )
    (net (code "115") (name "/RAM1_OE") (class "Default")
      (node (ref "HDR1") (pin "39") (pinfunction "39_39") (pintype "passive"))
      (node (ref "U1") (pin "179") (pinfunction "IO_179") (pintype "bidirectional"))
    )
    (net (code "116") (name "/RAM1_WE") (class "Default")
      (node (ref "HDR1") (pin "61") (pinfunction "61_61") (pintype "passive"))
      (node (ref "U1") (pin "192") (pinfunction "IO_192") (pintype "bidirectional"))
    )
    (net (code "117") (name "/RAM_ADDR0") (class "Default")
      (node (ref "HDR1") (pin "21") (pinfunction "21_21") (pintype "passive"))
      (node (ref "U1") (pin "167") (pinfunction "IO_167") (pintype "bidirectional"))
    )
    (net (code "118") (name "/RAM_ADDR1") (class "Default")
      (node (ref "HDR1") (pin "25") (pinfunction "25_25") (pintype "passive"))
      (node (ref "U1") (pin "169") (pinfunction "IO_169") (pintype "bidirectional"))
    )
    (net (code "119") (name "/RAM_ADDR2") (class "Default")
      (node (ref "HDR1") (pin "29") (pinfunction "29_29") (pintype "passive"))
      (node (ref "U1") (pin "173") (pinfunction "IO_173") (pintype "bidirectional"))
    )
    (net (code "120") (name "/RAM_ADDR3") (class "Default")
      (node (ref "HDR1") (pin "33") (pinfunction "33_33") (pintype "passive"))
      (node (ref "U1") (pin "175") (pinfunction "IO_175") (pintype "bidirectional"))
    )
    (net (code "121") (name "/RAM_ADDR4") (class "Default")
      (node (ref "HDR1") (pin "65") (pinfunction "65_65") (pintype "passive"))
      (node (ref "U1") (pin "194") (pinfunction "IO_194") (pintype "bidirectional"))
    )
    (net (code "122") (name "/RAM_ADDR5") (class "Default")
      (node (ref "HDR1") (pin "69") (pinfunction "69_69") (pintype "passive"))
      (node (ref "U1") (pin "197") (pinfunction "IO_197") (pintype "bidirectional"))
    )
    (net (code "123") (name "/RAM_ADDR6") (class "Default")
      (node (ref "HDR1") (pin "73") (pinfunction "73_73") (pintype "passive"))
      (node (ref "U1") (pin "199") (pinfunction "IO_199") (pintype "bidirectional"))
    )
    (net (code "124") (name "/RAM_ADDR7") (class "Default")
      (node (ref "HDR1") (pin "77") (pinfunction "77_77") (pintype "passive"))
      (node (ref "U1") (pin "201") (pinfunction "IO_201") (pintype "bidirectional"))
    )
    (net (code "125") (name "/RAM_ADDR8") (class "Default")
      (node (ref "HDR1") (pin "75") (pinfunction "75_75") (pintype "passive"))
      (node (ref "U1") (pin "200") (pinfunction "IO_200") (pintype "bidirectional"))
    )
    (net (code "126") (name "/RAM_ADDR9") (class "Default")
      (node (ref "HDR1") (pin "71") (pinfunction "71_71") (pintype "passive"))
      (node (ref "U1") (pin "198") (pinfunction "IO_198") (pintype "bidirectional"))
    )
    (net (code "127") (name "/RAM_ADDR10") (class "Default")
      (node (ref "HDR1") (pin "67") (pinfunction "67_67") (pintype "passive"))
      (node (ref "U1") (pin "196") (pinfunction "IO_196") (pintype "bidirectional"))
    )
    (net (code "128") (name "/RAM_ADDR11") (class "Default")
      (node (ref "HDR1") (pin "63") (pinfunction "63_63") (pintype "passive"))
      (node (ref "U1") (pin "193") (pinfunction "IO_193") (pintype "bidirectional"))
    )
    (net (code "129") (name "/RAM_ADDR12") (class "Default")
      (node (ref "HDR1") (pin "59") (pinfunction "59_59") (pintype "passive"))
      (node (ref "U1") (pin "191") (pinfunction "IO_191") (pintype "bidirectional"))
    )
    (net (code "130") (name "/RAM_ADDR13") (class "Default")
      (node (ref "HDR1") (pin "35") (pinfunction "35_35") (pintype "passive"))
      (node (ref "U1") (pin "176") (pinfunction "IO_176") (pintype "bidirectional"))
    )
    (net (code "131") (name "/RAM_ADDR14") (class "Default")
      (node (ref "HDR1") (pin "31") (pinfunction "31_31") (pintype "passive"))
      (node (ref "U1") (pin "174") (pinfunction "IO_174") (pintype "bidirectional"))
    )
    (net (code "132") (name "/RAM_ADDR15") (class "Default")
      (node (ref "HDR1") (pin "27") (pinfunction "27_27") (pintype "passive"))
      (node (ref "U1") (pin "172") (pinfunction "IO_172") (pintype "bidirectional"))
    )
    (net (code "133") (name "/RAM_ADDR16") (class "Default")
      (node (ref "HDR1") (pin "23") (pinfunction "23_23") (pintype "passive"))
      (node (ref "U1") (pin "168") (pinfunction "IO_168") (pintype "bidirectional"))
    )
    (net (code "134") (name "/RAM_CS") (class "Default")
      (node (ref "HDR1") (pin "37") (pinfunction "37_37") (pintype "passive"))
      (node (ref "U1") (pin "177") (pinfunction "IO_177") (pintype "bidirectional"))
    )
    (net (code "135") (name "/RED0") (class "Default")
      (node (ref "HDR1") (pin "6") (pinfunction "6_6") (pintype "passive"))
      (node (ref "U1") (pin "152") (pinfunction "IO_152") (pintype "bidirectional"))
    )
    (net (code "136") (name "/RED1") (class "Default")
      (node (ref "HDR1") (pin "8") (pinfunction "8_8") (pintype "passive"))
      (node (ref "U1") (pin "151") (pinfunction "IO_151") (pintype "bidirectional"))
    )
    (net (code "137") (name "/REF_CLK") (class "Default")
      (node (ref "HDR2") (pin "4") (pinfunction "4_4") (pintype "passive"))
      (node (ref "U1") (pin "128") (pinfunction "IO/GL3_128") (pintype "bidirectional"))
    )
    (net (code "138") (name "/SCL") (class "Default")
      (node (ref "HDR2") (pin "5") (pinfunction "5_5") (pintype "passive"))
      (node (ref "U1") (pin "113") (pinfunction "IO_113") (pintype "bidirectional"))
    )
    (net (code "139") (name "/SDA") (class "Default")
      (node (ref "HDR2") (pin "3") (pinfunction "3_3") (pintype "passive"))
      (node (ref "U1") (pin "112") (pinfunction "IO_112") (pintype "bidirectional"))
    )
    (net (code "140") (name "/SP0") (class "Default")
      (node (ref "HDR2") (pin "79") (pinfunction "79_79") (pintype "passive"))
      (node (ref "U1") (pin "47") (pinfunction "IO_47") (pintype "bidirectional"))
    )
    (net (code "141") (name "/SP1") (class "Default")
      (node (ref "HDR2") (pin "81") (pinfunction "81_81") (pintype "passive"))
      (node (ref "U1") (pin "48") (pinfunction "IO_48") (pintype "bidirectional"))
    )
    (net (code "142") (name "/SP2") (class "Default")
      (node (ref "HDR2") (pin "83") (pinfunction "83_83") (pintype "passive"))
      (node (ref "U1") (pin "49") (pinfunction "IO_49") (pintype "bidirectional"))
    )
    (net (code "143") (name "/SP3") (class "Default")
      (node (ref "HDR2") (pin "85") (pinfunction "85_85") (pintype "passive"))
      (node (ref "U1") (pin "50") (pinfunction "IO_50") (pintype "bidirectional"))
    )
    (net (code "144") (name "/SP4") (class "Default")
      (node (ref "HDR2") (pin "87") (pinfunction "87_87") (pintype "passive"))
      (node (ref "U1") (pin "51") (pinfunction "IO_51") (pintype "bidirectional"))
    )
    (net (code "145") (name "/SP5") (class "Default")
      (node (ref "HDR2") (pin "89") (pinfunction "89_89") (pintype "passive"))
      (node (ref "U1") (pin "54") (pinfunction "IO_54") (pintype "bidirectional"))
    )
    (net (code "146") (name "/SP6") (class "Default")
      (node (ref "HDR2") (pin "91") (pinfunction "91_91") (pintype "passive"))
      (node (ref "U1") (pin "55") (pinfunction "IO_55") (pintype "bidirectional"))
    )
    (net (code "147") (name "/SP7") (class "Default")
      (node (ref "HDR2") (pin "92") (pinfunction "92_92") (pintype "passive"))
      (node (ref "U1") (pin "56") (pinfunction "IO_56") (pintype "bidirectional"))
    )
    (net (code "148") (name "/SP8") (class "Default")
      (node (ref "HDR2") (pin "90") (pinfunction "90_90") (pintype "passive"))
      (node (ref "U1") (pin "57") (pinfunction "IO_57") (pintype "bidirectional"))
    )
    (net (code "149") (name "/SP9") (class "Default")
      (node (ref "HDR2") (pin "88") (pinfunction "88_88") (pintype "passive"))
      (node (ref "U1") (pin "58") (pinfunction "IO_58") (pintype "bidirectional"))
    )
    (net (code "150") (name "/SP10") (class "Default")
      (node (ref "HDR2") (pin "86") (pinfunction "86_86") (pintype "passive"))
      (node (ref "U1") (pin "59") (pinfunction "IO_59") (pintype "bidirectional"))
    )
    (net (code "151") (name "/SP11") (class "Default")
      (node (ref "HDR2") (pin "84") (pinfunction "84_84") (pintype "passive"))
    )
    (net (code "152") (name "/SP12") (class "Default")
      (node (ref "HDR2") (pin "82") (pinfunction "82_82") (pintype "passive"))
    )
    (net (code "153") (name "/SP13") (class "Default")
      (node (ref "HDR2") (pin "80") (pinfunction "80_80") (pintype "passive"))
    )
    (net (code "154") (name "/SP14") (class "Default")
      (node (ref "HDR2") (pin "78") (pinfunction "78_78") (pintype "passive"))
    )
    (net (code "155") (name "/SP15") (class "Default")
      (node (ref "HDR2") (pin "76") (pinfunction "76_76") (pintype "passive"))
    )
    (net (code "156") (name "/SPI_CLK") (class "Default")
      (node (ref "HDR1") (pin "46") (pinfunction "46_46") (pintype "passive"))
      (node (ref "U1") (pin "10") (pinfunction "IO_10") (pintype "bidirectional"))
    )
    (net (code "157") (name "/SPI_DIN") (class "Default")
      (node (ref "HDR1") (pin "44") (pinfunction "44_44") (pintype "passive"))
      (node (ref "U1") (pin "11") (pinfunction "IO_11") (pintype "bidirectional"))
    )
    (net (code "158") (name "/SPI_DOUT") (class "Default")
      (node (ref "HDR1") (pin "50") (pinfunction "50_50") (pintype "passive"))
      (node (ref "U1") (pin "8") (pinfunction "IO_8") (pintype "bidirectional"))
    )
    (net (code "159") (name "/SPI_MODE") (class "Default")
      (node (ref "HDR1") (pin "52") (pinfunction "52_52") (pintype "passive"))
      (node (ref "U1") (pin "7") (pinfunction "IO_7") (pintype "bidirectional"))
    )
    (net (code "160") (name "/SPI_SEL") (class "Default")
      (node (ref "HDR1") (pin "48") (pinfunction "48_48") (pintype "passive"))
      (node (ref "U1") (pin "9") (pinfunction "IO_9") (pintype "bidirectional"))
    )
    (net (code "161") (name "/SW0") (class "Default")
      (node (ref "HDR2") (pin "44") (pinfunction "44_44") (pintype "passive"))
      (node (ref "U1") (pin "78") (pinfunction "IO_78") (pintype "bidirectional"))
    )
    (net (code "162") (name "/SW1") (class "Default")
      (node (ref "HDR2") (pin "46") (pinfunction "46_46") (pintype "passive"))
      (node (ref "U1") (pin "77") (pinfunction "IO_77") (pintype "bidirectional"))
    )
    (net (code "163") (name "/SW2") (class "Default")
      (node (ref "HDR2") (pin "48") (pinfunction "48_48") (pintype "passive"))
      (node (ref "U1") (pin "76") (pinfunction "IO_76") (pintype "bidirectional"))
    )
    (net (code "164") (name "/SW3") (class "Default")
      (node (ref "HDR2") (pin "50") (pinfunction "50_50") (pintype "passive"))
      (node (ref "U1") (pin "75") (pinfunction "IO_75") (pintype "bidirectional"))
    )
    (net (code "165") (name "/SW4") (class "Default")
      (node (ref "HDR2") (pin "52") (pinfunction "52_52") (pintype "passive"))
      (node (ref "U1") (pin "74") (pinfunction "IO_74") (pintype "bidirectional"))
    )
    (net (code "166") (name "/SW5") (class "Default")
      (node (ref "HDR2") (pin "54") (pinfunction "54_54") (pintype "passive"))
      (node (ref "U1") (pin "73") (pinfunction "IO_73") (pintype "bidirectional"))
    )
    (net (code "167") (name "/SW6") (class "Default")
      (node (ref "HDR2") (pin "56") (pinfunction "56_56") (pintype "passive"))
      (node (ref "U1") (pin "70") (pinfunction "IO_70") (pintype "bidirectional"))
    )
    (net (code "168") (name "/SW7") (class "Default")
      (node (ref "HDR2") (pin "58") (pinfunction "58_58") (pintype "passive"))
      (node (ref "U1") (pin "69") (pinfunction "IO_69") (pintype "bidirectional"))
    )
    (net (code "169") (name "/SWC0") (class "Default")
      (node (ref "HDR2") (pin "18") (pinfunction "18_18") (pintype "passive"))
      (node (ref "U1") (pin "94") (pinfunction "IO_94") (pintype "bidirectional"))
    )
    (net (code "170") (name "/SWC1") (class "Default")
      (node (ref "HDR2") (pin "16") (pinfunction "16_16") (pintype "passive"))
      (node (ref "U1") (pin "95") (pinfunction "IO_95") (pintype "bidirectional"))
    )
    (net (code "171") (name "/SWC2") (class "Default")
      (node (ref "HDR2") (pin "14") (pinfunction "14_14") (pintype "passive"))
      (node (ref "U1") (pin "96") (pinfunction "IO_96") (pintype "bidirectional"))
    )
    (net (code "172") (name "/SWC3") (class "Default")
      (node (ref "HDR2") (pin "6") (pinfunction "6_6") (pintype "passive"))
      (node (ref "U1") (pin "111") (pinfunction "IO_111") (pintype "bidirectional"))
    )
    (net (code "173") (name "/SWR0") (class "Default")
      (node (ref "HDR2") (pin "20") (pinfunction "20_20") (pintype "passive"))
      (node (ref "U1") (pin "93") (pinfunction "IO_93") (pintype "bidirectional"))
    )
    (net (code "174") (name "/SWR1") (class "Default")
      (node (ref "HDR2") (pin "12") (pinfunction "12_12") (pintype "passive"))
      (node (ref "U1") (pin "98") (pinfunction "IO_98") (pintype "bidirectional"))
    )
    (net (code "175") (name "/SWR2") (class "Default")
      (node (ref "HDR2") (pin "10") (pinfunction "10_10") (pintype "passive"))
      (node (ref "U1") (pin "99") (pinfunction "IO_99") (pintype "bidirectional"))
    )
    (net (code "176") (name "/SWR3") (class "Default")
      (node (ref "HDR2") (pin "8") (pinfunction "8_8") (pintype "passive"))
      (node (ref "U1") (pin "100") (pinfunction "IO_100") (pintype "bidirectional"))
    )
    (net (code "177") (name "/TEST") (class "Default")
      (node (ref "HDR1") (pin "81") (pinfunction "81_81") (pintype "passive"))
      (node (ref "U1") (pin "203") (pinfunction "IO_203") (pintype "bidirectional"))
    )
    (net (code "178") (name "/VDRIVE") (class "Default")
      (node (ref "HDR1") (pin "20") (pinfunction "20_20") (pintype "passive"))
      (node (ref "U1") (pin "145") (pinfunction "IO_145") (pintype "bidirectional"))
    )
    (net (code "179") (name "/VREF") (class "Default")
      (node (ref "HDR1") (pin "91") (pinfunction "91_91") (pintype "passive"))
      (node (ref "R1") (pin "2") (pinfunction "2_2") (pintype "passive"))
      (node (ref "R2") (pin "1") (pinfunction "1_1") (pintype "passive"))
    )
    (net (code "180") (name "5V") (class "Default")
      (node (ref "C29") (pin "1") (pinfunction "1_1") (pintype "passive"))
      (node (ref "C31") (pin "1") (pinfunction "1_1") (pintype "passive"))
      (node (ref "C33") (pin "1") (pinfunction "1_1") (pintype "passive"))
      (node (ref "C35") (pin "1") (pinfunction "1_1") (pintype "passive"))
      (node (ref "HDR1") (pin "97") (pinfunction "97_97") (pintype "passive"))
      (node (ref "HDR1") (pin "99") (pinfunction "99_99") (pintype "passive"))
      (node (ref "HDR2") (pin "97") (pinfunction "97_97") (pintype "passive"))
      (node (ref "HDR2") (pin "99") (pinfunction "99_99") (pintype "passive"))
      (node (ref "L1") (pin "1") (pinfunction "1_1") (pintype "passive"))
      (node (ref "L2") (pin "1") (pinfunction "1_1") (pintype "passive"))
      (node (ref "U2") (pin "5") (pinfunction "VIN_5") (pintype "power_in"))
      (node (ref "U3") (pin "5") (pinfunction "VIN_5") (pintype "power_in"))
    )
    (net (code "181") (name "GND") (class "Default")
      (node (ref "C1") (pin "2") (pinfunction "2_2") (pintype "passive"))
      (node (ref "C10") (pin "2") (pinfunction "2_2") (pintype "passive"))
      (node (ref "C11") (pin "1") (pinfunction "1_1") (pintype "passive"))
      (node (ref "C12") (pin "1") (pinfunction "1_1") (pintype "passive"))
      (node (ref "C13") (pin "1") (pinfunction "1_1") (pintype "passive"))
      (node (ref "C14") (pin "1") (pinfunction "1_1") (pintype "passive"))
      (node (ref "C15") (pin "1") (pinfunction "1_1") (pintype "passive"))
      (node (ref "C16") (pin "1") (pinfunction "1_1") (pintype "passive"))
      (node (ref "C17") (pin "1") (pinfunction "1_1") (pintype "passive"))
      (node (ref "C18") (pin "1") (pinfunction "1_1") (pintype "passive"))
      (node (ref "C19") (pin "1") (pinfunction "1_1") (pintype "passive"))
      (node (ref "C2") (pin "1") (pinfunction "1_1") (pintype "passive"))
      (node (ref "C20") (pin "1") (pinfunction "1_1") (pintype "passive"))
      (node (ref "C21") (pin "1") (pinfunction "1_1") (pintype "passive"))
      (node (ref "C22") (pin "2") (pinfunction "2_2") (pintype "passive"))
      (node (ref "C23") (pin "2") (pinfunction "2_2") (pintype "passive"))
      (node (ref "C24") (pin "2") (pinfunction "2_2") (pintype "passive"))
      (node (ref "C25") (pin "2") (pinfunction "2_2") (pintype "passive"))
      (node (ref "C26") (pin "2") (pinfunction "2_2") (pintype "passive"))
      (node (ref "C28") (pin "2") (pinfunction "2_2") (pintype "passive"))
      (node (ref "C29") (pin "2") (pinfunction "2_2") (pintype "passive"))
      (node (ref "C3") (pin "1") (pinfunction "1_1") (pintype "passive"))
      (node (ref "C30") (pin "2") (pinfunction "2_2") (pintype "passive"))
      (node (ref "C31") (pin "2") (pinfunction "2_2") (pintype "passive"))
      (node (ref "C33") (pin "2") (pinfunction "2_2") (pintype "passive"))
      (node (ref "C34") (pin "1") (pinfunction "1_1") (pintype "passive"))
      (node (ref "C35") (pin "2") (pinfunction "2_2") (pintype "passive"))
      (node (ref "C36") (pin "2") (pinfunction "2_2") (pintype "passive"))
      (node (ref "C4") (pin "1") (pinfunction "1_1") (pintype "passive"))
      (node (ref "C5") (pin "1") (pinfunction "1_1") (pintype "passive"))
      (node (ref "C6") (pin "1") (pinfunction "1_1") (pintype "passive"))
      (node (ref "C7") (pin "1") (pinfunction "1_1") (pintype "passive"))
      (node (ref "C8") (pin "1") (pinfunction "1_1") (pintype "passive"))
      (node (ref "C9") (pin "1") (pinfunction "1_1") (pintype "passive"))
      (node (ref "D2") (pin "2") (pinfunction "K_2") (pintype "passive"))
      (node (ref "HDR1") (pin "1") (pinfunction "1_1") (pintype "passive"))
      (node (ref "HDR1") (pin "100") (pinfunction "100_100") (pintype "passive"))
      (node (ref "HDR1") (pin "36") (pinfunction "36_36") (pintype "passive"))
      (node (ref "HDR1") (pin "40") (pinfunction "40_40") (pintype "passive"))
      (node (ref "HDR1") (pin "98") (pinfunction "98_98") (pintype "passive"))
      (node (ref "HDR2") (pin "1") (pinfunction "1_1") (pintype "passive"))
      (node (ref "HDR2") (pin "100") (pinfunction "100_100") (pintype "passive"))
      (node (ref "HDR2") (pin "98") (pinfunction "98_98") (pintype "passive"))
      (node (ref "LED2") (pin "2") (pinfunction "K_2") (pintype "passive"))
      (node (ref "R10") (pin "2") (pinfunction "2_2") (pintype "passive"))
      (node (ref "R12") (pin "2") (pinfunction "2_2") (pintype "passive"))
      (node (ref "R13") (pin "1") (pinfunction "1_1") (pintype "passive"))
      (node (ref "R2") (pin "2") (pinfunction "2_2") (pintype "passive"))
      (node (ref "R6") (pin "2") (pinfunction "2_2") (pintype "passive"))
      (node (ref "R7") (pin "2") (pinfunction "2_2") (pintype "passive"))
      (node (ref "R9") (pin "2") (pinfunction "2_2") (pintype "passive"))
      (node (ref "U1") (pin "1") (pinfunction "GND_1") (pintype "power_in"))
      (node (ref "U1") (pin "105") (pinfunction "GND_105") (pintype "power_in"))
      (node (ref "U1") (pin "122") (pinfunction "GND_122") (pintype "power_in"))
      (node (ref "U1") (pin "130") (pinfunction "GND_130") (pintype "power_in"))
      (node (ref "U1") (pin "133") (pinfunction "AGND_133") (pintype "power_in"))
      (node (ref "U1") (pin "141") (pinfunction "GND_141") (pintype "power_in"))
      (node (ref "U1") (pin "156") (pinfunction "GND_156") (pintype "power_in"))
      (node (ref "U1") (pin "162") (pinfunction "GND_162") (pintype "power_in"))
      (node (ref "U1") (pin "17") (pinfunction "GND_17") (pintype "power_in"))
      (node (ref "U1") (pin "178") (pinfunction "GND_178") (pintype "power_in"))
      (node (ref "U1") (pin "195") (pinfunction "GND_195") (pintype "power_in"))
      (node (ref "U1") (pin "25") (pinfunction "AGND_25") (pintype "power_in"))
      (node (ref "U1") (pin "29") (pinfunction "GND_29") (pintype "power_in"))
      (node (ref "U1") (pin "41") (pinfunction "GND_41") (pintype "power_in"))
      (node (ref "U1") (pin "52") (pinfunction "GND_52") (pintype "power_in"))
      (node (ref "U1") (pin "65") (pinfunction "GND_65") (pintype "power_in"))
      (node (ref "U1") (pin "81") (pinfunction "GND_81") (pintype "power_in"))
      (node (ref "U1") (pin "97") (pinfunction "GND_97") (pintype "power_in"))
      (node (ref "U2") (pin "2") (pinfunction "GND_2") (pintype "power_in"))
      (node (ref "U3") (pin "2") (pinfunction "GND_2") (pintype "power_in"))
      (node (ref "U4") (pin "3") (pinfunction "GND_3") (pintype "power_in"))
    )
    (net (code "182") (name "Net-(D1-A)") (class "Default")
      (node (ref "D1") (pin "1") (pinfunction "A_1") (pintype "passive"))
      (node (ref "L1") (pin "2") (pinfunction "2_2") (pintype "passive"))
      (node (ref "U2") (pin "1") (pinfunction "SW_1") (pintype "passive"))
    )
    (net (code "183") (name "Net-(D2-A)") (class "Default")
      (node (ref "C32") (pin "2") (pinfunction "2_2") (pintype "passive"))
      (node (ref "D2") (pin "1") (pinfunction "A_1") (pintype "passive"))
      (node (ref "L3") (pin "1") (pinfunction "1_1") (pintype "passive"))
    )
    (net (code "184") (name "Net-(LED1-A)") (class "Default")
      (node (ref "LED1") (pin "1") (pinfunction "A_1") (pintype "passive"))
      (node (ref "R14") (pin "1") (pinfunction "1_1") (pintype "passive"))
    )
    (net (code "185") (name "Net-(LED1-K)") (class "Default")
      (node (ref "LED1") (pin "2") (pinfunction "K_2") (pintype "passive"))
      (node (ref "U4") (pin "4") (pinfunction "Y_4") (pintype "output"))
    )
    (net (code "186") (name "Net-(LED2-A)") (class "Default")
      (node (ref "LED2") (pin "1") (pinfunction "A_1") (pintype "passive"))
      (node (ref "R3") (pin "2") (pinfunction "2_2") (pintype "passive"))
    )
    (net (code "187") (name "Net-(U2-FB)") (class "Default")
      (node (ref "C27") (pin "2") (pinfunction "2_2") (pintype "passive"))
      (node (ref "R6") (pin "1") (pinfunction "1_1") (pintype "passive"))
      (node (ref "R7") (pin "1") (pinfunction "1_1") (pintype "passive"))
      (node (ref "R8") (pin "2") (pinfunction "2_2") (pintype "passive"))
      (node (ref "U2") (pin "3") (pinfunction "FB_3") (pintype "power_in"))
    )
    (net (code "188") (name "Net-(U3-FB)") (class "Default")
      (node (ref "C37") (pin "2") (pinfunction "2_2") (pintype "passive"))
      (node (ref "R10") (pin "1") (pinfunction "1_1") (pintype "passive"))
      (node (ref "R11") (pin "2") (pinfunction "2_2") (pintype "passive"))
      (node (ref "R9") (pin "1") (pinfunction "1_1") (pintype "passive"))
      (node (ref "U3") (pin "3") (pinfunction "FB_3") (pintype "power_in"))
    )
    (net (code "189") (name "Net-(U3-SW)") (class "Default")
      (node (ref "C32") (pin "1") (pinfunction "1_1") (pintype "passive"))
      (node (ref "L2") (pin "2") (pinfunction "2_2") (pintype "passive"))
      (node (ref "U3") (pin "1") (pinfunction "SW_1") (pintype "passive"))
    )
    (net (code "190") (name "VCC") (class "Default")
      (node (ref "C10") (pin "1") (pinfunction "1_1") (pintype "passive"))
      (node (ref "C11") (pin "2") (pinfunction "2_2") (pintype "passive"))
      (node (ref "C12") (pin "2") (pinfunction "2_2") (pintype "passive"))
      (node (ref "C13") (pin "2") (pinfunction "2_2") (pintype "passive"))
      (node (ref "C14") (pin "2") (pinfunction "2_2") (pintype "passive"))
      (node (ref "C15") (pin "2") (pinfunction "2_2") (pintype "passive"))
      (node (ref "C16") (pin "2") (pinfunction "2_2") (pintype "passive"))
      (node (ref "C17") (pin "2") (pinfunction "2_2") (pintype "passive"))
      (node (ref "C18") (pin "2") (pinfunction "2_2") (pintype "passive"))
      (node (ref "C19") (pin "2") (pinfunction "2_2") (pintype "passive"))
      (node (ref "C20") (pin "2") (pinfunction "2_2") (pintype "passive"))
      (node (ref "C21") (pin "2") (pinfunction "2_2") (pintype "passive"))
      (node (ref "C24") (pin "1") (pinfunction "1_1") (pintype "passive"))
      (node (ref "C25") (pin "1") (pinfunction "1_1") (pintype "passive"))
      (node (ref "HDR1") (pin "34") (pinfunction "34_34") (pintype "passive"))
      (node (ref "HDR1") (pin "38") (pinfunction "38_38") (pintype "passive"))
      (node (ref "HDR1") (pin "42") (pinfunction "42_42") (pintype "passive"))
      (node (ref "HDR1") (pin "74") (pinfunction "74_74") (pintype "passive"))
      (node (ref "HDR1") (pin "94") (pinfunction "94_94") (pintype "passive"))
      (node (ref "HDR1") (pin "96") (pinfunction "96_96") (pintype "passive"))
      (node (ref "HDR2") (pin "94") (pinfunction "94_94") (pintype "passive"))
      (node (ref "HDR2") (pin "96") (pinfunction "96_96") (pintype "passive"))
      (node (ref "R14") (pin "2") (pinfunction "2_2") (pintype "passive"))
      (node (ref "R3") (pin "1") (pinfunction "1_1") (pintype "passive"))
      (node (ref "U1") (pin "104") (pinfunction "VDDP_104") (pintype "power_in"))
      (node (ref "U1") (pin "109") (pinfunction "~{TRST}_109") (pintype "input"))
      (node (ref "U1") (pin "123") (pinfunction "VDDP_123") (pintype "power_in"))
      (node (ref "U1") (pin "138") (pinfunction "VDDP_138") (pintype "power_in"))
      (node (ref "U1") (pin "157") (pinfunction "VDDP_157") (pintype "power_in"))
      (node (ref "U1") (pin "170") (pinfunction "VDDP_170") (pintype "power_in"))
      (node (ref "U1") (pin "186") (pinfunction "VDDP_186") (pintype "power_in"))
      (node (ref "U1") (pin "208") (pinfunction "VDDP_208") (pintype "power_in"))
      (node (ref "U1") (pin "22") (pinfunction "VDDP_22") (pintype "power_in"))
      (node (ref "U1") (pin "40") (pinfunction "VDDP_40") (pintype "power_in"))
      (node (ref "U1") (pin "53") (pinfunction "VDDP_53") (pintype "power_in"))
      (node (ref "U1") (pin "72") (pinfunction "VDDP_72") (pintype "power_in"))
      (node (ref "U1") (pin "89") (pinfunction "VDDP_89") (pintype "power_in"))
      (node (ref "U4") (pin "5") (pinfunction "VCC_5") (pintype "power_in"))
    )
    (net (code "191") (name "VCCINT") (class "Default")
      (node (ref "C2") (pin "2") (pinfunction "2_2") (pintype "passive"))
      (node (ref "C22") (pin "1") (pinfunction "1_1") (pintype "passive"))
      (node (ref "C23") (pin "1") (pinfunction "1_1") (pintype "passive"))
      (node (ref "C3") (pin "2") (pinfunction "2_2") (pintype "passive"))
      (node (ref "C4") (pin "2") (pinfunction "2_2") (pintype "passive"))
      (node (ref "C5") (pin "2") (pinfunction "2_2") (pintype "passive"))
      (node (ref "C6") (pin "2") (pinfunction "2_2") (pintype "passive"))
      (node (ref "C7") (pin "2") (pinfunction "2_2") (pintype "passive"))
      (node (ref "C8") (pin "2") (pinfunction "2_2") (pintype "passive"))
      (node (ref "C9") (pin "2") (pinfunction "2_2") (pintype "passive"))
      (node (ref "HDR1") (pin "93") (pinfunction "93_93") (pintype "passive"))
      (node (ref "HDR1") (pin "95") (pinfunction "95_95") (pintype "passive"))
      (node (ref "HDR2") (pin "93") (pinfunction "93_93") (pintype "passive"))
      (node (ref "HDR2") (pin "95") (pinfunction "95_95") (pintype "passive"))
      (node (ref "R1") (pin "1") (pinfunction "1_1") (pintype "passive"))
      (node (ref "R4") (pin "1") (pinfunction "1_1") (pintype "passive"))
      (node (ref "R5") (pin "1") (pinfunction "1_1") (pintype "passive"))
      (node (ref "U1") (pin "126") (pinfunction "VDD_126") (pintype "power_in"))
      (node (ref "U1") (pin "142") (pinfunction "VDD_142") (pintype "power_in"))
      (node (ref "U1") (pin "16") (pinfunction "VDD_16") (pintype "power_in"))
      (node (ref "U1") (pin "171") (pinfunction "VDD_171") (pintype "power_in"))
      (node (ref "U1") (pin "187") (pinfunction "VDD_187") (pintype "power_in"))
      (node (ref "U1") (pin "36") (pinfunction "VDD_36") (pintype "power_in"))
      (node (ref "U1") (pin "71") (pinfunction "VDD_71") (pintype "power_in"))
      (node (ref "U1") (pin "88") (pinfunction "VDD_88") (pintype "power_in"))
    )
    (net (code "192") (name "VPN") (class "Default")
      (node (ref "C34") (pin "2") (pinfunction "2_2") (pintype "passive"))
      (node (ref "C36") (pin "1") (pinfunction "1_1") (pintype "passive"))
      (node (ref "C37") (pin "1") (pinfunction "1_1") (pintype "passive"))
      (node (ref "L3") (pin "2") (pinfunction "2_2") (pintype "passive"))
      (node (ref "R11") (pin "1") (pinfunction "1_1") (pintype "passive"))
      (node (ref "U1") (pin "107") (pinfunction "VPN_107") (pintype "power_in"))
    )
    (net (code "193") (name "VPP") (class "Default")
      (node (ref "C27") (pin "1") (pinfunction "1_1") (pintype "passive"))
      (node (ref "C28") (pin "1") (pinfunction "1_1") (pintype "passive"))
      (node (ref "C30") (pin "1") (pinfunction "1_1") (pintype "passive"))
      (node (ref "D1") (pin "2") (pinfunction "K_2") (pintype "passive"))
      (node (ref "R8") (pin "1") (pinfunction "1_1") (pintype "passive"))
      (node (ref "U1") (pin "106") (pinfunction "VPP_106") (pintype "power_in"))
    )
    (net (code "194") (name "unconnected-(U1A-IO-Pad6)") (class "Default")
      (node (ref "U1") (pin "6") (pinfunction "IO_6") (pintype "bidirectional+no_connect"))
    )
    (net (code "195") (name "unconnected-(U1C-NPECL1-Pad26)") (class "Default")
      (node (ref "U1") (pin "26") (pinfunction "NPECL1_26") (pintype "input+no_connect"))
    )
    (net (code "196") (name "unconnected-(U1C-NPECL2-Pad132)") (class "Default")
      (node (ref "U1") (pin "132") (pinfunction "NPECL2_132") (pintype "input+no_connect"))
    )
    (net (code "197") (name "unconnected-(U1C-PPECL1_(I{slash}P)-Pad28)") (class "Default")
      (node (ref "U1") (pin "28") (pinfunction "PPECL1_(I/P)_28") (pintype "input+no_connect"))
    )
    (net (code "198") (name "unconnected-(U1C-PPECL2_(I{slash}P)-Pad129)") (class "Default")
      (node (ref "U1") (pin "129") (pinfunction "PPECL2_(I/P)_129") (pintype "input+no_connect"))
    )
    (net (code "199") (name "unconnected-(U4-NC-Pad1)") (class "Default")
      (node (ref "U4") (pin "1") (pinfunction "NC_1") (pintype "passive"))
    )
  )
)
